# BusPirate-v3_6a.net
KiCad netlist of a schematic drawn in EAGLE
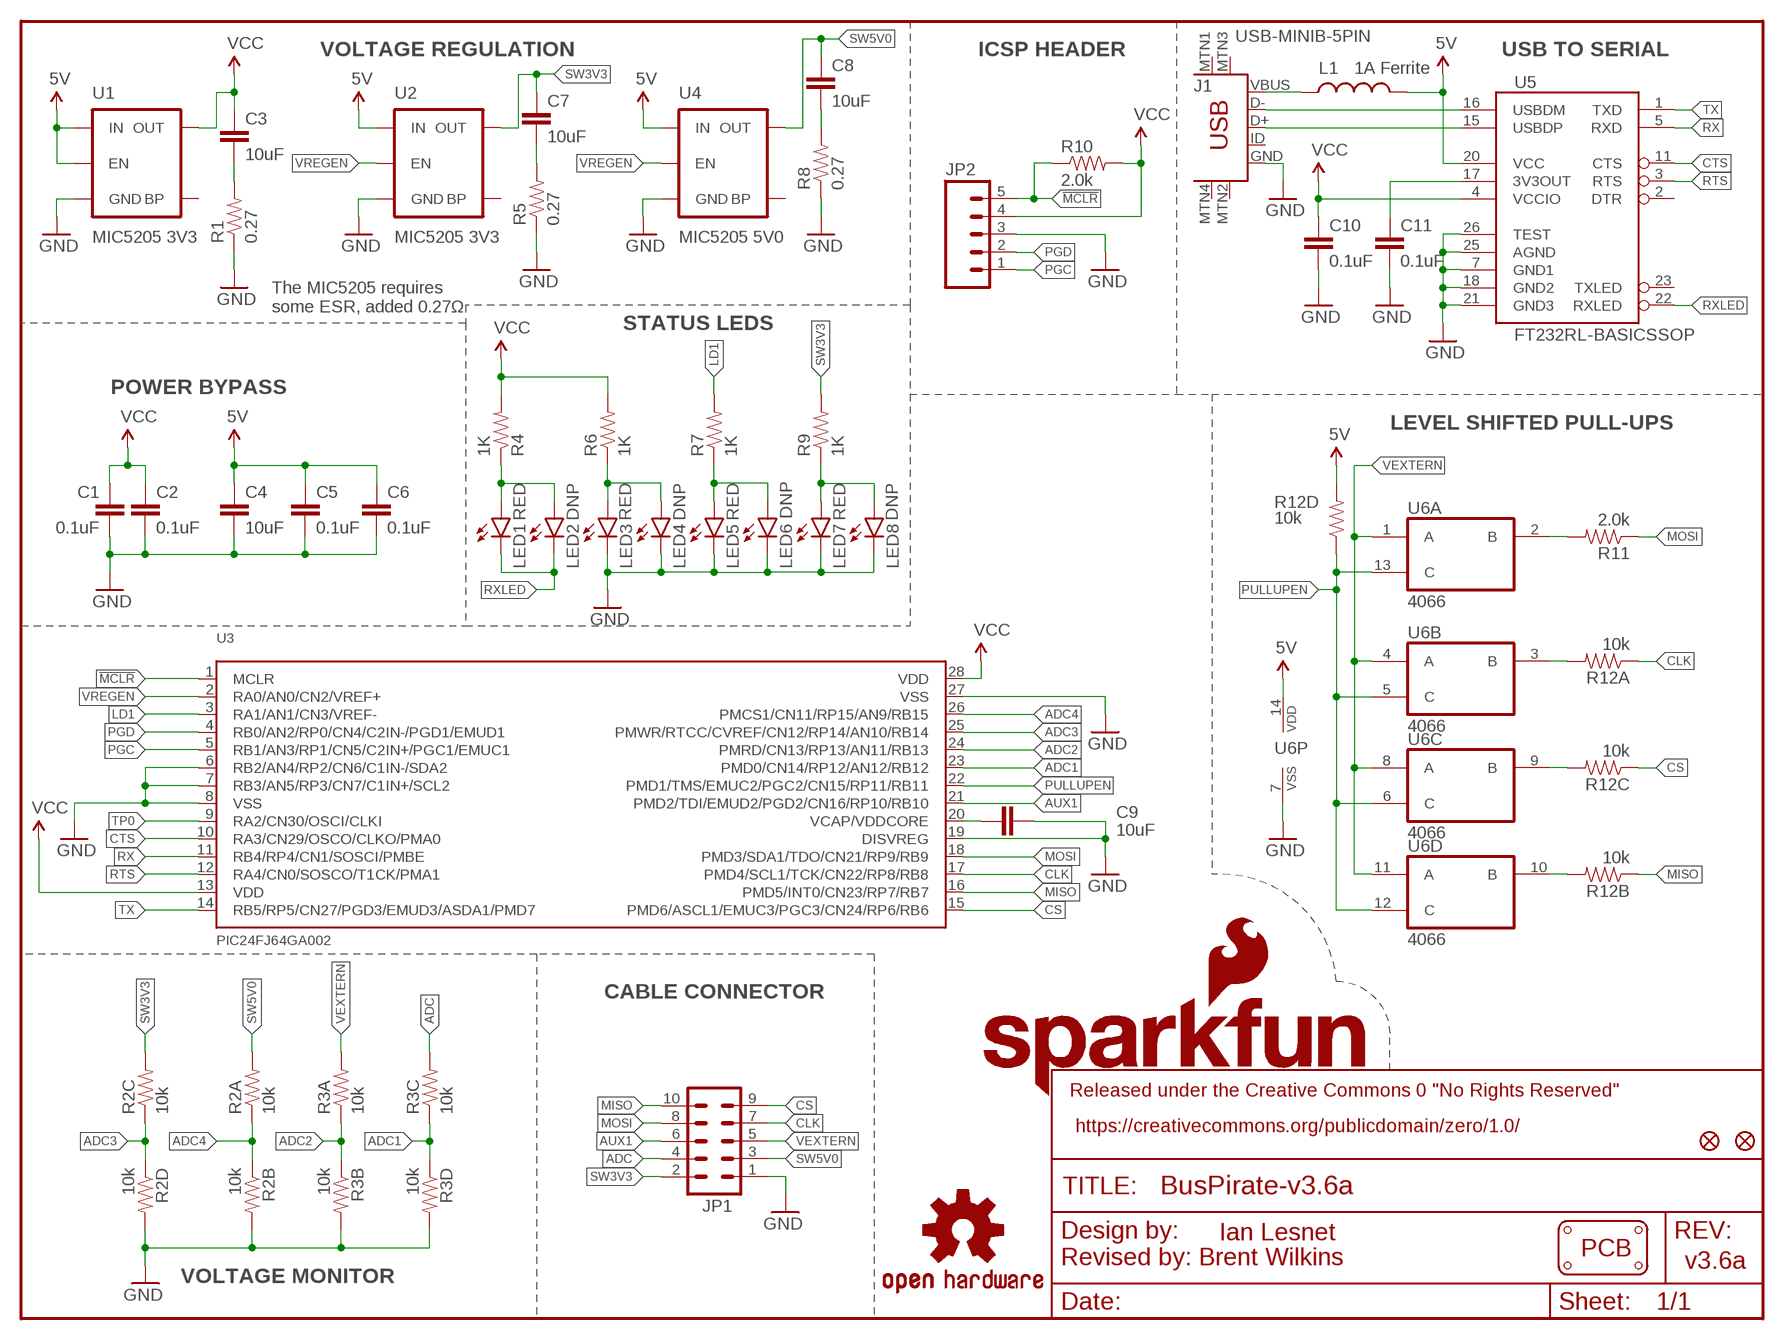
[diagram p0: schematic, sheet 1]

(export (version "E")
  (design (tool "Eeschema 10.0.6"))
  (components
    (comp (ref "C1")
      (value "0.1uF")
      (footprint "eagle-import:0603-CAP")
      (libsource (lib "eagle-import") (part "0.1UF-25V(+80/-20%)(0603)"))
    )
    (comp (ref "C2")
      (value "0.1uF")
      (footprint "eagle-import:0603-CAP")
      (libsource (lib "eagle-import") (part "0.1UF-25V(+80/-20%)(0603)"))
    )
    (comp (ref "C3")
      (value "10uF")
      (footprint "eagle-import:0805-CAP")
      (libsource (lib "eagle-import") (part "10UF10V10%(0805)"))
    )
    (comp (ref "C4")
      (value "10uF")
      (footprint "eagle-import:0805-CAP")
      (libsource (lib "eagle-import") (part "10UF10V10%(0805)"))
    )
    (comp (ref "C5")
      (value "0.1uF")
      (footprint "eagle-import:0603-CAP")
      (libsource (lib "eagle-import") (part "0.1UF-25V(+80/-20%)(0603)"))
    )
    (comp (ref "C6")
      (value "0.1uF")
      (footprint "eagle-import:0603-CAP")
      (libsource (lib "eagle-import") (part "0.1UF-25V(+80/-20%)(0603)"))
    )
    (comp (ref "C7")
      (value "10uF")
      (footprint "eagle-import:0805-CAP")
      (libsource (lib "eagle-import") (part "10UF10V10%(0805)"))
    )
    (comp (ref "C8")
      (value "10uF")
      (footprint "eagle-import:0805-CAP")
      (libsource (lib "eagle-import") (part "10UF10V10%(0805)"))
    )
    (comp (ref "C9")
      (value "10uF")
      (footprint "eagle-import:0805-CAP")
      (libsource (lib "eagle-import") (part "10UF10V10%(0805)"))
    )
    (comp (ref "C10")
      (value "0.1uF")
      (footprint "eagle-import:0603-CAP")
      (libsource (lib "eagle-import") (part "0.1UF-25V(+80/-20%)(0603)"))
    )
    (comp (ref "C11")
      (value "0.1uF")
      (footprint "eagle-import:0603-CAP")
      (libsource (lib "eagle-import") (part "0.1UF-25V(+80/-20%)(0603)"))
    )
    (comp (ref "FID1")
      (value "FIDUCIAL1X2")
      (footprint "eagle-import:FIDUCIAL-1X2")
      (libsource (lib "eagle-import") (part "FIDUCIAL1X2"))
    )
    (comp (ref "FID2")
      (value "FIDUCIAL1X2")
      (footprint "eagle-import:FIDUCIAL-1X2")
      (libsource (lib "eagle-import") (part "FIDUCIAL1X2"))
    )
    (comp (ref "J1")
      (value "USB-MINIB-5PIN")
      (footprint "eagle-import:USB-MINIB")
      (libsource (lib "eagle-import") (part "USB-MINIB-5PIN"))
    )
    (comp (ref "JP1")
      (value "M05X2SHD_SMD")
      (footprint "eagle-import:2X5-SHROUDED_SMD")
      (libsource (lib "eagle-import") (part "M05X2SHD_SMD"))
    )
    (comp (ref "JP2")
      (value "M05PTH")
      (footprint "eagle-import:1X05")
      (libsource (lib "eagle-import") (part "M05PTH"))
    )
    (comp (ref "L1")
      (value "1A Ferrite")
      (footprint "eagle-import:0603")
      (libsource (lib "eagle-import") (part "INDUCTOR0603"))
    )
    (comp (ref "LED1")
      (value "RED")
      (footprint "eagle-import:LED-0603")
      (fields (field (name "PROD_ID") "DIO-00819"))
      (libsource (lib "eagle-import") (part "LED-RED0603"))
    )
    (comp (ref "LED2")
      (value "DNP")
      (footprint "eagle-import:LED-0603")
      (libsource (lib "eagle-import") (part "LED-RED0603"))
    )
    (comp (ref "LED3")
      (value "RED")
      (footprint "eagle-import:LED-0603")
      (libsource (lib "eagle-import") (part "LED-RED0603"))
    )
    (comp (ref "LED4")
      (value "DNP")
      (footprint "eagle-import:LED-0603")
      (libsource (lib "eagle-import") (part "LED-RED0603"))
    )
    (comp (ref "LED5")
      (value "RED")
      (footprint "eagle-import:LED-0603")
      (libsource (lib "eagle-import") (part "LED-RED0603"))
    )
    (comp (ref "LED6")
      (value "DNP")
      (footprint "eagle-import:LED-0603")
      (libsource (lib "eagle-import") (part "LED-RED0603"))
    )
    (comp (ref "LED7")
      (value "RED")
      (footprint "eagle-import:LED-0603")
      (libsource (lib "eagle-import") (part "LED-RED0603"))
    )
    (comp (ref "LED8")
      (value "DNP")
      (footprint "eagle-import:LED-0603")
      (libsource (lib "eagle-import") (part "LED-RED0603"))
    )
    (comp (ref "LOGO1")
      (value "OSHW-LOGOL")
      (footprint "eagle-import:OSHW-LOGO-L")
      (libsource (lib "eagle-import") (part "OSHW-LOGOL"))
    )
    (comp (ref "LOGO2")
      (value "SFE_LOGO_NAME_FLAME.1_INCH")
      (footprint "eagle-import:SFE_LOGO_NAME_FLAME_.1")
      (libsource (lib "eagle-import") (part "SFE_LOGO_NAME_FLAME.1_INCH"))
    )
    (comp (ref "PCB1")
      (value "PCB_DP_RECTANGLE-37X60")
      (footprint "eagle-import:DP6037_V1")
      (libsource (lib "eagle-import") (part "PCB_DP_RECTANGLE-37X60"))
    )
    (comp (ref "R1")
      (value "0.27")
      (footprint "eagle-import:0603")
      (fields (field (name "PROD_ID") "RES-08787"))
      (libsource (lib "eagle-import") (part "0OHM-1/10W-5%(0603)"))
    )
    (comp (ref "R2")
      (value "10k")
      (footprint "eagle-import:4XARRAY")
      (fields (field (name "PROD_ID") "RES-13167"))
      (libsource (lib "eagle-import") (part "CAY16-F4"))
    )
    (comp (ref "R3")
      (value "10k")
      (footprint "eagle-import:4XARRAY")
      (fields (field (name "PROD_ID") "RES-13167"))
      (libsource (lib "eagle-import") (part "CAY16-F4"))
    )
    (comp (ref "R4")
      (value "1K")
      (footprint "eagle-import:0603-RES")
      (libsource (lib "eagle-import") (part "1KOHM-1/10W-1%(0603)"))
    )
    (comp (ref "R5")
      (value "0.27")
      (footprint "eagle-import:0603")
      (fields (field (name "PROD_ID") "RES-08787"))
      (libsource (lib "eagle-import") (part "0OHM-1/10W-5%(0603)"))
    )
    (comp (ref "R6")
      (value "1K")
      (footprint "eagle-import:0603-RES")
      (libsource (lib "eagle-import") (part "1KOHM-1/10W-1%(0603)"))
    )
    (comp (ref "R7")
      (value "1K")
      (footprint "eagle-import:0603-RES")
      (libsource (lib "eagle-import") (part "1KOHM-1/10W-1%(0603)"))
    )
    (comp (ref "R8")
      (value "0.27")
      (footprint "eagle-import:0603")
      (fields (field (name "PROD_ID") "RES-08787"))
      (libsource (lib "eagle-import") (part "0OHM-1/10W-5%(0603)"))
    )
    (comp (ref "R9")
      (value "1K")
      (footprint "eagle-import:0603-RES")
      (libsource (lib "eagle-import") (part "1KOHM-1/10W-1%(0603)"))
    )
    (comp (ref "R10")
      (value "2.0k")
      (footprint "eagle-import:0603-RES")
      (libsource (lib "eagle-import") (part "2.0KOHM1/10W5%(0603)"))
    )
    (comp (ref "R11")
      (value "2.0k")
      (footprint "eagle-import:0603-RES")
      (libsource (lib "eagle-import") (part "2.0KOHM1/10W5%(0603)"))
    )
    (comp (ref "R12")
      (value "10k")
      (footprint "eagle-import:4XARRAY")
      (fields (field (name "PROD_ID") "RES-13167"))
      (libsource (lib "eagle-import") (part "CAY16-F4"))
    )
    (comp (ref "U1")
      (value "MIC5205 3V3")
      (footprint "eagle-import:SOT23-5")
      (libsource (lib "eagle-import") (part "MIC52053.3V"))
    )
    (comp (ref "U2")
      (value "MIC5205 3V3")
      (footprint "eagle-import:SOT23-5")
      (libsource (lib "eagle-import") (part "MIC52053.3V"))
    )
    (comp (ref "U3")
      (value "PIC24FJ64GA002")
      (footprint "eagle-import:SSOP28")
      (fields (field (name "PROD_ID") "IC-09426"))
      (libsource (lib "eagle-import") (part "PIC24FJ64GA002"))
    )
    (comp (ref "U4")
      (value "MIC5205 5V0")
      (footprint "eagle-import:SOT23-5")
      (libsource (lib "eagle-import") (part "MIC52055V"))
    )
    (comp (ref "U5")
      (value "FT232RL-BASICSSOP")
      (footprint "eagle-import:SSOP28DB")
      (libsource (lib "eagle-import") (part "FT232RL-BASICSSOP"))
    )
    (comp (ref "U6")
      (value "4066")
      (footprint "eagle-import:TSSOP14")
      (fields (field (name "PROD_ID") "IC-13191"))
      (libsource (lib "eagle-import") (part "4066"))
    )
  )
  (nets
    (net (code "1") (name "/~{MCLR}") (class "Default")
      (node (ref "JP2") (pin "5") (pinfunction "5_5") (pintype "passive"))
      (node (ref "R10") (pin "1") (pinfunction "1_1") (pintype "passive"))
      (node (ref "U3") (pin "1") (pinfunction "MCLR_1") (pintype "input"))
    )
    (net (code "2") (name "5V") (class "Default")
      (node (ref "C4") (pin "1") (pinfunction "1_1") (pintype "passive"))
      (node (ref "C5") (pin "1") (pinfunction "1_1") (pintype "passive"))
      (node (ref "C6") (pin "1") (pinfunction "1_1") (pintype "passive"))
      (node (ref "L1") (pin "2") (pinfunction "2_2") (pintype "passive"))
      (node (ref "R12") (pin "5") (pinfunction "2_5") (pintype "passive"))
      (node (ref "U1") (pin "1") (pinfunction "IN_1") (pintype "input"))
      (node (ref "U1") (pin "3") (pinfunction "EN_3") (pintype "input"))
      (node (ref "U2") (pin "1") (pinfunction "IN_1") (pintype "input"))
      (node (ref "U4") (pin "1") (pinfunction "IN_1") (pintype "input"))
      (node (ref "U5") (pin "20") (pinfunction "VCC_20") (pintype "power_in"))
      (node (ref "U6") (pin "14") (pinfunction "VDD_14") (pintype "power_in"))
    )
    (net (code "3") (name "ADC") (class "Default")
      (node (ref "JP1") (pin "4") (pinfunction "4_4") (pintype "passive"))
      (node (ref "R3") (pin "6") (pinfunction "2_6") (pintype "passive"))
    )
    (net (code "4") (name "ADC1") (class "Default")
      (node (ref "R3") (pin "3") (pinfunction "1_3") (pintype "passive"))
      (node (ref "R3") (pin "4") (pinfunction "1_4") (pintype "passive"))
      (node (ref "U3") (pin "23") (pinfunction "PMD0/CN14/RP12/AN12/RB12_23") (pintype "bidirectional"))
    )
    (net (code "5") (name "ADC2") (class "Default")
      (node (ref "R3") (pin "1") (pinfunction "1_1") (pintype "passive"))
      (node (ref "R3") (pin "2") (pinfunction "1_2") (pintype "passive"))
      (node (ref "U3") (pin "24") (pinfunction "PMRD/CN13/RP13/AN11/RB13_24") (pintype "bidirectional"))
    )
    (net (code "6") (name "ADC3") (class "Default")
      (node (ref "R2") (pin "3") (pinfunction "1_3") (pintype "passive"))
      (node (ref "R2") (pin "4") (pinfunction "1_4") (pintype "passive"))
      (node (ref "U3") (pin "25") (pinfunction "PMWR/RTCC/CVREF/CN12/RP14/AN10/RB14_25") (pintype "bidirectional"))
    )
    (net (code "7") (name "ADC4") (class "Default")
      (node (ref "R2") (pin "1") (pinfunction "1_1") (pintype "passive"))
      (node (ref "R2") (pin "2") (pinfunction "1_2") (pintype "passive"))
      (node (ref "U3") (pin "26") (pinfunction "PMCS1/CN11/RP15/AN9/RB15_26") (pintype "bidirectional"))
    )
    (net (code "8") (name "AUX1") (class "Default")
      (node (ref "JP1") (pin "6") (pinfunction "6_6") (pintype "passive"))
      (node (ref "U3") (pin "21") (pinfunction "PMD2/TDI/EMUD2/PGD2/CN16/RP10/RB10_21") (pintype "bidirectional"))
    )
    (net (code "9") (name "CLK") (class "Default")
      (node (ref "JP1") (pin "7") (pinfunction "7_7") (pintype "passive"))
      (node (ref "R12") (pin "1") (pinfunction "1_1") (pintype "passive"))
      (node (ref "U3") (pin "17") (pinfunction "PMD4/SCL1/TCK/CN22/RP8/RB8_17") (pintype "bidirectional"))
    )
    (net (code "10") (name "CS") (class "Default")
      (node (ref "JP1") (pin "9") (pinfunction "9_9") (pintype "passive"))
      (node (ref "R12") (pin "3") (pinfunction "1_3") (pintype "passive"))
      (node (ref "U3") (pin "15") (pinfunction "PMD6/ASCL1/EMUC3/PGC3/CN24/RP6/RB6_15") (pintype "bidirectional"))
    )
    (net (code "11") (name "CTS") (class "Default")
      (node (ref "U3") (pin "10") (pinfunction "RA3/CN29/OSCO/CLKO/PMA0_10") (pintype "bidirectional"))
      (node (ref "U5") (pin "11") (pinfunction "CTS_11") (pintype "bidirectional"))
    )
    (net (code "12") (name "GND") (class "Default")
      (node (ref "C1") (pin "2") (pinfunction "2_2") (pintype "passive"))
      (node (ref "C10") (pin "2") (pinfunction "2_2") (pintype "passive"))
      (node (ref "C11") (pin "2") (pinfunction "2_2") (pintype "passive"))
      (node (ref "C2") (pin "2") (pinfunction "2_2") (pintype "passive"))
      (node (ref "C4") (pin "2") (pinfunction "2_2") (pintype "passive"))
      (node (ref "C5") (pin "2") (pinfunction "2_2") (pintype "passive"))
      (node (ref "C6") (pin "2") (pinfunction "2_2") (pintype "passive"))
      (node (ref "C9") (pin "2") (pinfunction "2_2") (pintype "passive"))
      (node (ref "J1") (pin "GND") (pinfunction "GND_GND") (pintype "bidirectional"))
      (node (ref "JP1") (pin "1") (pinfunction "1_1") (pintype "passive"))
      (node (ref "JP2") (pin "3") (pinfunction "3_3") (pintype "passive"))
      (node (ref "LED3") (pin "C") (pinfunction "C_C") (pintype "passive"))
      (node (ref "LED4") (pin "C") (pinfunction "C_C") (pintype "passive"))
      (node (ref "LED5") (pin "C") (pinfunction "C_C") (pintype "passive"))
      (node (ref "LED6") (pin "C") (pinfunction "C_C") (pintype "passive"))
      (node (ref "LED7") (pin "C") (pinfunction "C_C") (pintype "passive"))
      (node (ref "LED8") (pin "C") (pinfunction "C_C") (pintype "passive"))
      (node (ref "R1") (pin "1") (pinfunction "1_1") (pintype "passive"))
      (node (ref "R2") (pin "5") (pinfunction "2_5") (pintype "passive"))
      (node (ref "R2") (pin "7") (pinfunction "2_7") (pintype "passive"))
      (node (ref "R3") (pin "5") (pinfunction "2_5") (pintype "passive"))
      (node (ref "R3") (pin "7") (pinfunction "2_7") (pintype "passive"))
      (node (ref "R5") (pin "1") (pinfunction "1_1") (pintype "passive"))
      (node (ref "R8") (pin "1") (pinfunction "1_1") (pintype "passive"))
      (node (ref "U1") (pin "2") (pinfunction "GND_2") (pintype "input"))
      (node (ref "U2") (pin "2") (pinfunction "GND_2") (pintype "input"))
      (node (ref "U3") (pin "19") (pinfunction "DISVREG_19") (pintype "power_in"))
      (node (ref "U3") (pin "27") (pinfunction "VSS_27") (pintype "power_in"))
      (node (ref "U3") (pin "6") (pinfunction "RB2/AN4/RP2/CN6/C1IN-/SDA2_6") (pintype "bidirectional"))
      (node (ref "U3") (pin "7") (pinfunction "RB3/AN5/RP3/CN7/C1IN+/SCL2_7") (pintype "bidirectional"))
      (node (ref "U3") (pin "8") (pinfunction "VSS_8") (pintype "power_in"))
      (node (ref "U4") (pin "2") (pinfunction "GND_2") (pintype "input"))
      (node (ref "U5") (pin "18") (pinfunction "GND2_18") (pintype "power_in"))
      (node (ref "U5") (pin "21") (pinfunction "GND3_21") (pintype "power_in"))
      (node (ref "U5") (pin "25") (pinfunction "AGND_25") (pintype "power_in"))
      (node (ref "U5") (pin "26") (pinfunction "TEST_26") (pintype "input"))
      (node (ref "U5") (pin "7") (pinfunction "GND1_7") (pintype "power_in"))
      (node (ref "U6") (pin "7") (pinfunction "VSS_7") (pintype "power_in"))
    )
    (net (code "13") (name "LD1") (class "Default")
      (node (ref "R7") (pin "2") (pinfunction "2_2") (pintype "passive"))
      (node (ref "U3") (pin "3") (pinfunction "RA1/AN1/CN3/VREF-_3") (pintype "bidirectional"))
    )
    (net (code "14") (name "MISO") (class "Default")
      (node (ref "JP1") (pin "10") (pinfunction "10_10") (pintype "passive"))
      (node (ref "R12") (pin "2") (pinfunction "1_2") (pintype "passive"))
      (node (ref "U3") (pin "16") (pinfunction "PMD5/INT0/CN23/RP7/RB7_16") (pintype "bidirectional"))
    )
    (net (code "15") (name "MOSI") (class "Default")
      (node (ref "JP1") (pin "8") (pinfunction "8_8") (pintype "passive"))
      (node (ref "R11") (pin "1") (pinfunction "1_1") (pintype "passive"))
      (node (ref "U3") (pin "18") (pinfunction "PMD3/SDA1/TDO/CN21/RP9/RB9_18") (pintype "bidirectional"))
    )
    (net (code "16") (name "Net-(C3-Pad2)") (class "Default")
      (node (ref "C3") (pin "2") (pinfunction "2_2") (pintype "passive"))
      (node (ref "R1") (pin "2") (pinfunction "2_2") (pintype "passive"))
    )
    (net (code "17") (name "Net-(C7-Pad2)") (class "Default")
      (node (ref "C7") (pin "2") (pinfunction "2_2") (pintype "passive"))
      (node (ref "R5") (pin "2") (pinfunction "2_2") (pintype "passive"))
    )
    (net (code "18") (name "Net-(C8-Pad2)") (class "Default")
      (node (ref "C8") (pin "2") (pinfunction "2_2") (pintype "passive"))
      (node (ref "R8") (pin "2") (pinfunction "2_2") (pintype "passive"))
    )
    (net (code "19") (name "Net-(J1-PadVBUS)") (class "Default")
      (node (ref "J1") (pin "VBUS") (pinfunction "VBUS_VBUS") (pintype "bidirectional"))
      (node (ref "L1") (pin "1") (pinfunction "1_1") (pintype "passive"))
    )
    (net (code "20") (name "Net-(LED1-PadA)") (class "Default")
      (node (ref "LED1") (pin "A") (pinfunction "A_A") (pintype "passive"))
      (node (ref "LED2") (pin "A") (pinfunction "A_A") (pintype "passive"))
      (node (ref "R4") (pin "1") (pinfunction "1_1") (pintype "passive"))
    )
    (net (code "21") (name "Net-(LED3-PadA)") (class "Default")
      (node (ref "LED3") (pin "A") (pinfunction "A_A") (pintype "passive"))
      (node (ref "LED4") (pin "A") (pinfunction "A_A") (pintype "passive"))
      (node (ref "R6") (pin "1") (pinfunction "1_1") (pintype "passive"))
    )
    (net (code "22") (name "Net-(LED5-PadA)") (class "Default")
      (node (ref "LED5") (pin "A") (pinfunction "A_A") (pintype "passive"))
      (node (ref "LED6") (pin "A") (pinfunction "A_A") (pintype "passive"))
      (node (ref "R7") (pin "1") (pinfunction "1_1") (pintype "passive"))
    )
    (net (code "23") (name "Net-(LED7-PadA)") (class "Default")
      (node (ref "LED7") (pin "A") (pinfunction "A_A") (pintype "passive"))
      (node (ref "LED8") (pin "A") (pinfunction "A_A") (pintype "passive"))
      (node (ref "R9") (pin "1") (pinfunction "1_1") (pintype "passive"))
    )
    (net (code "24") (name "Net-(R12A-2)") (class "Default")
      (node (ref "R12") (pin "8") (pinfunction "2_8") (pintype "passive"))
      (node (ref "U6") (pin "3") (pinfunction "B_3") (pintype "tri_state"))
    )
    (net (code "25") (name "Net-(R12B-2)") (class "Default")
      (node (ref "R12") (pin "7") (pinfunction "2_7") (pintype "passive"))
      (node (ref "U6") (pin "10") (pinfunction "B_10") (pintype "tri_state"))
    )
    (net (code "26") (name "Net-(R12C-2)") (class "Default")
      (node (ref "R12") (pin "6") (pinfunction "2_6") (pintype "passive"))
      (node (ref "U6") (pin "9") (pinfunction "B_9") (pintype "tri_state"))
    )
    (net (code "27") (name "Net-(U3-VCAP{slash}VDDCORE)") (class "Default")
      (node (ref "C9") (pin "1") (pinfunction "1_1") (pintype "passive"))
      (node (ref "U3") (pin "20") (pinfunction "VCAP/VDDCORE_20") (pintype "power_in"))
    )
    (net (code "28") (name "Net-(U5-3V3OUT)") (class "Default")
      (node (ref "C11") (pin "1") (pinfunction "1_1") (pintype "passive"))
      (node (ref "U5") (pin "17") (pinfunction "3V3OUT_17") (pintype "output"))
    )
    (net (code "29") (name "Net-(U5-USBDM)") (class "Default")
      (node (ref "J1") (pin "D-") (pinfunction "D-_D-") (pintype "bidirectional"))
      (node (ref "U5") (pin "16") (pinfunction "USBDM_16") (pintype "bidirectional"))
    )
    (net (code "30") (name "Net-(U5-USBDP)") (class "Default")
      (node (ref "J1") (pin "D+") (pinfunction "D+_D+") (pintype "bidirectional"))
      (node (ref "U5") (pin "15") (pinfunction "USBDP_15") (pintype "bidirectional"))
    )
    (net (code "31") (name "Net-(U6A-B)") (class "Default")
      (node (ref "R11") (pin "2") (pinfunction "2_2") (pintype "passive"))
      (node (ref "U6") (pin "2") (pinfunction "B_2") (pintype "tri_state"))
    )
    (net (code "32") (name "PGC") (class "Default")
      (node (ref "JP2") (pin "1") (pinfunction "1_1") (pintype "passive"))
      (node (ref "U3") (pin "5") (pinfunction "RB1/AN3/RP1/CN5/C2IN+/PGC1/EMUC1_5") (pintype "bidirectional"))
    )
    (net (code "33") (name "PGD") (class "Default")
      (node (ref "JP2") (pin "2") (pinfunction "2_2") (pintype "passive"))
      (node (ref "U3") (pin "4") (pinfunction "RB0/AN2/RP0/CN4/C2IN-/PGD1/EMUD1_4") (pintype "bidirectional"))
    )
    (net (code "34") (name "PULLUPEN") (class "Default")
      (node (ref "R12") (pin "4") (pinfunction "1_4") (pintype "passive"))
      (node (ref "U3") (pin "22") (pinfunction "PMD1/TMS/EMUC2/PGC2/CN15/RP11/RB11_22") (pintype "bidirectional"))
      (node (ref "U6") (pin "12") (pinfunction "C_12") (pintype "input"))
      (node (ref "U6") (pin "13") (pinfunction "C_13") (pintype "input"))
      (node (ref "U6") (pin "5") (pinfunction "C_5") (pintype "input"))
      (node (ref "U6") (pin "6") (pinfunction "C_6") (pintype "input"))
    )
    (net (code "35") (name "RTS") (class "Default")
      (node (ref "U3") (pin "12") (pinfunction "RA4/CN0/SOSCO/T1CK/PMA1_12") (pintype "bidirectional"))
      (node (ref "U5") (pin "3") (pinfunction "RTS_3") (pintype "bidirectional"))
    )
    (net (code "36") (name "RX") (class "Default")
      (node (ref "U3") (pin "11") (pinfunction "RB4/RP4/CN1/SOSCI/PMBE_11") (pintype "bidirectional"))
      (node (ref "U5") (pin "5") (pinfunction "RXD_5") (pintype "input"))
    )
    (net (code "37") (name "RXLED") (class "Default")
      (node (ref "LED1") (pin "C") (pinfunction "C_C") (pintype "passive"))
      (node (ref "LED2") (pin "C") (pinfunction "C_C") (pintype "passive"))
      (node (ref "U5") (pin "22") (pinfunction "RXLED_22") (pintype "bidirectional"))
    )
    (net (code "38") (name "SW3V3") (class "Default")
      (node (ref "C7") (pin "1") (pinfunction "1_1") (pintype "passive"))
      (node (ref "JP1") (pin "2") (pinfunction "2_2") (pintype "passive"))
      (node (ref "R2") (pin "6") (pinfunction "2_6") (pintype "passive"))
      (node (ref "R9") (pin "2") (pinfunction "2_2") (pintype "passive"))
      (node (ref "U2") (pin "5") (pinfunction "OUT_5") (pintype "passive"))
    )
    (net (code "39") (name "SW5V0") (class "Default")
      (node (ref "C8") (pin "1") (pinfunction "1_1") (pintype "passive"))
      (node (ref "JP1") (pin "3") (pinfunction "3_3") (pintype "passive"))
      (node (ref "R2") (pin "8") (pinfunction "2_8") (pintype "passive"))
      (node (ref "U4") (pin "5") (pinfunction "OUT_5") (pintype "passive"))
    )
    (net (code "40") (name "TP0") (class "Default")
      (node (ref "U3") (pin "9") (pinfunction "RA2/CN30/OSCI/CLKI_9") (pintype "bidirectional"))
    )
    (net (code "41") (name "TX") (class "Default")
      (node (ref "U3") (pin "14") (pinfunction "RB5/RP5/CN27/PGD3/EMUD3/ASDA1/PMD7_14") (pintype "bidirectional"))
      (node (ref "U5") (pin "1") (pinfunction "TXD_1") (pintype "output"))
    )
    (net (code "42") (name "VCC") (class "Default")
      (node (ref "C1") (pin "1") (pinfunction "1_1") (pintype "passive"))
      (node (ref "C10") (pin "1") (pinfunction "1_1") (pintype "passive"))
      (node (ref "C2") (pin "1") (pinfunction "1_1") (pintype "passive"))
      (node (ref "C3") (pin "1") (pinfunction "1_1") (pintype "passive"))
      (node (ref "JP2") (pin "4") (pinfunction "4_4") (pintype "passive"))
      (node (ref "R10") (pin "2") (pinfunction "2_2") (pintype "passive"))
      (node (ref "R4") (pin "2") (pinfunction "2_2") (pintype "passive"))
      (node (ref "R6") (pin "2") (pinfunction "2_2") (pintype "passive"))
      (node (ref "U1") (pin "5") (pinfunction "OUT_5") (pintype "passive"))
      (node (ref "U3") (pin "13") (pinfunction "VDD_13") (pintype "power_in"))
      (node (ref "U3") (pin "28") (pinfunction "VDD_28") (pintype "power_in"))
      (node (ref "U5") (pin "4") (pinfunction "VCCIO_4") (pintype "power_in"))
    )
    (net (code "43") (name "VEXTERN") (class "Default")
      (node (ref "JP1") (pin "5") (pinfunction "5_5") (pintype "passive"))
      (node (ref "R3") (pin "8") (pinfunction "2_8") (pintype "passive"))
      (node (ref "U6") (pin "1") (pinfunction "A_1") (pintype "tri_state"))
      (node (ref "U6") (pin "11") (pinfunction "A_11") (pintype "tri_state"))
      (node (ref "U6") (pin "4") (pinfunction "A_4") (pintype "tri_state"))
      (node (ref "U6") (pin "8") (pinfunction "A_8") (pintype "tri_state"))
    )
    (net (code "44") (name "VREGEN") (class "Default")
      (node (ref "U2") (pin "3") (pinfunction "EN_3") (pintype "input"))
      (node (ref "U3") (pin "2") (pinfunction "RA0/AN0/CN2/VREF+_2") (pintype "bidirectional"))
      (node (ref "U4") (pin "3") (pinfunction "EN_3") (pintype "input"))
    )
    (net (code "45") (name "unconnected-(J1-MTN1-PadMTN3)") (class "Default")
      (node (ref "J1") (pin "MTN3") (pinfunction "MTN1_MTN3") (pintype "bidirectional"))
    )
    (net (code "46") (name "unconnected-(J1-MTN2-PadMTN1)") (class "Default")
      (node (ref "J1") (pin "MTN1") (pinfunction "MTN2_MTN1") (pintype "bidirectional"))
    )
    (net (code "47") (name "unconnected-(J1-MTN3-PadMTN2)") (class "Default")
      (node (ref "J1") (pin "MTN2") (pinfunction "MTN3_MTN2") (pintype "bidirectional"))
    )
    (net (code "48") (name "unconnected-(J1-PadID)") (class "Default")
      (node (ref "J1") (pin "ID") (pinfunction "ID_ID") (pintype "bidirectional"))
    )
    (net (code "49") (name "unconnected-(J1-PadMTN4)") (class "Default")
      (node (ref "J1") (pin "MTN4") (pinfunction "MTN4_MTN4") (pintype "bidirectional"))
    )
    (net (code "50") (name "unconnected-(U1-BP-Pad4)") (class "Default")
      (node (ref "U1") (pin "4") (pinfunction "BP_4") (pintype "input"))
    )
    (net (code "51") (name "unconnected-(U2-BP-Pad4)") (class "Default")
      (node (ref "U2") (pin "4") (pinfunction "BP_4") (pintype "input"))
    )
    (net (code "52") (name "unconnected-(U4-BP-Pad4)") (class "Default")
      (node (ref "U4") (pin "4") (pinfunction "BP_4") (pintype "input"))
    )
    (net (code "53") (name "unconnected-(U5-DTR-Pad2)") (class "Default")
      (node (ref "U5") (pin "2") (pinfunction "DTR_2") (pintype "bidirectional"))
    )
    (net (code "54") (name "unconnected-(U5-TXLED-Pad23)") (class "Default")
      (node (ref "U5") (pin "23") (pinfunction "TXLED_23") (pintype "bidirectional"))
    )
  )
)
